# Button.net
KiCad netlist of a schematic drawn in Altium Designer
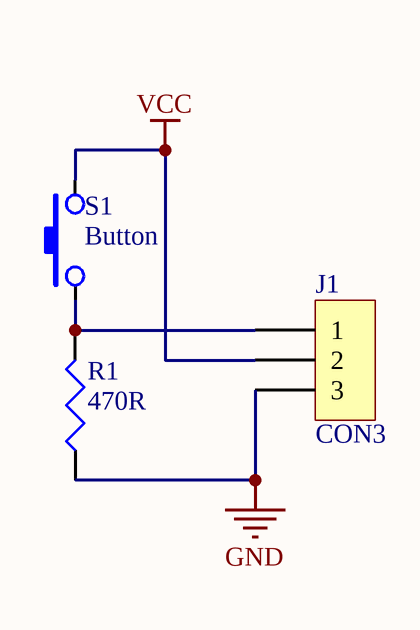
[diagram p0: Button.SchDoc]

(export (version "E")
  (design (tool "Eeschema 10.0.6"))
  (components
    (comp (ref "J1")
      (value "CON3")
      (footprint "DevModule")
      (description "Connector")
      (libsource (lib "CON系列") (part "CON3"))
    )
    (comp (ref "R1") (value "470R") (footprint "6-0805_N") (libsource (lib "电阻器") (part "RES1_1")))
    (comp (ref "S1") (value "Button") (footprint "KFCA06") (libsource (lib "手动开关") (part "SW-PB")))
  )
  (nets
    (net (code "1") (name "GND") (class "Default")
      (node (ref "J1") (pin "3") (pinfunction "3_3") (pintype "passive"))
      (node (ref "R1") (pin "1") (pinfunction "1_1") (pintype "passive"))
    )
    (net (code "2") (name "Net-(J1-Pad1)") (class "Default")
      (node (ref "J1") (pin "1") (pinfunction "1_1") (pintype "passive"))
      (node (ref "R1") (pin "2") (pinfunction "2_2") (pintype "passive"))
      (node (ref "S1") (pin "1") (pinfunction "1_1") (pintype "passive"))
    )
    (net (code "3") (name "VCC") (class "Default")
      (node (ref "J1") (pin "2") (pinfunction "2_2") (pintype "passive"))
      (node (ref "S1") (pin "2") (pinfunction "2_2") (pintype "passive"))
    )
  )
)
